# l-band-frontend.net
KiCad netlist of a schematic drawn in EAGLE
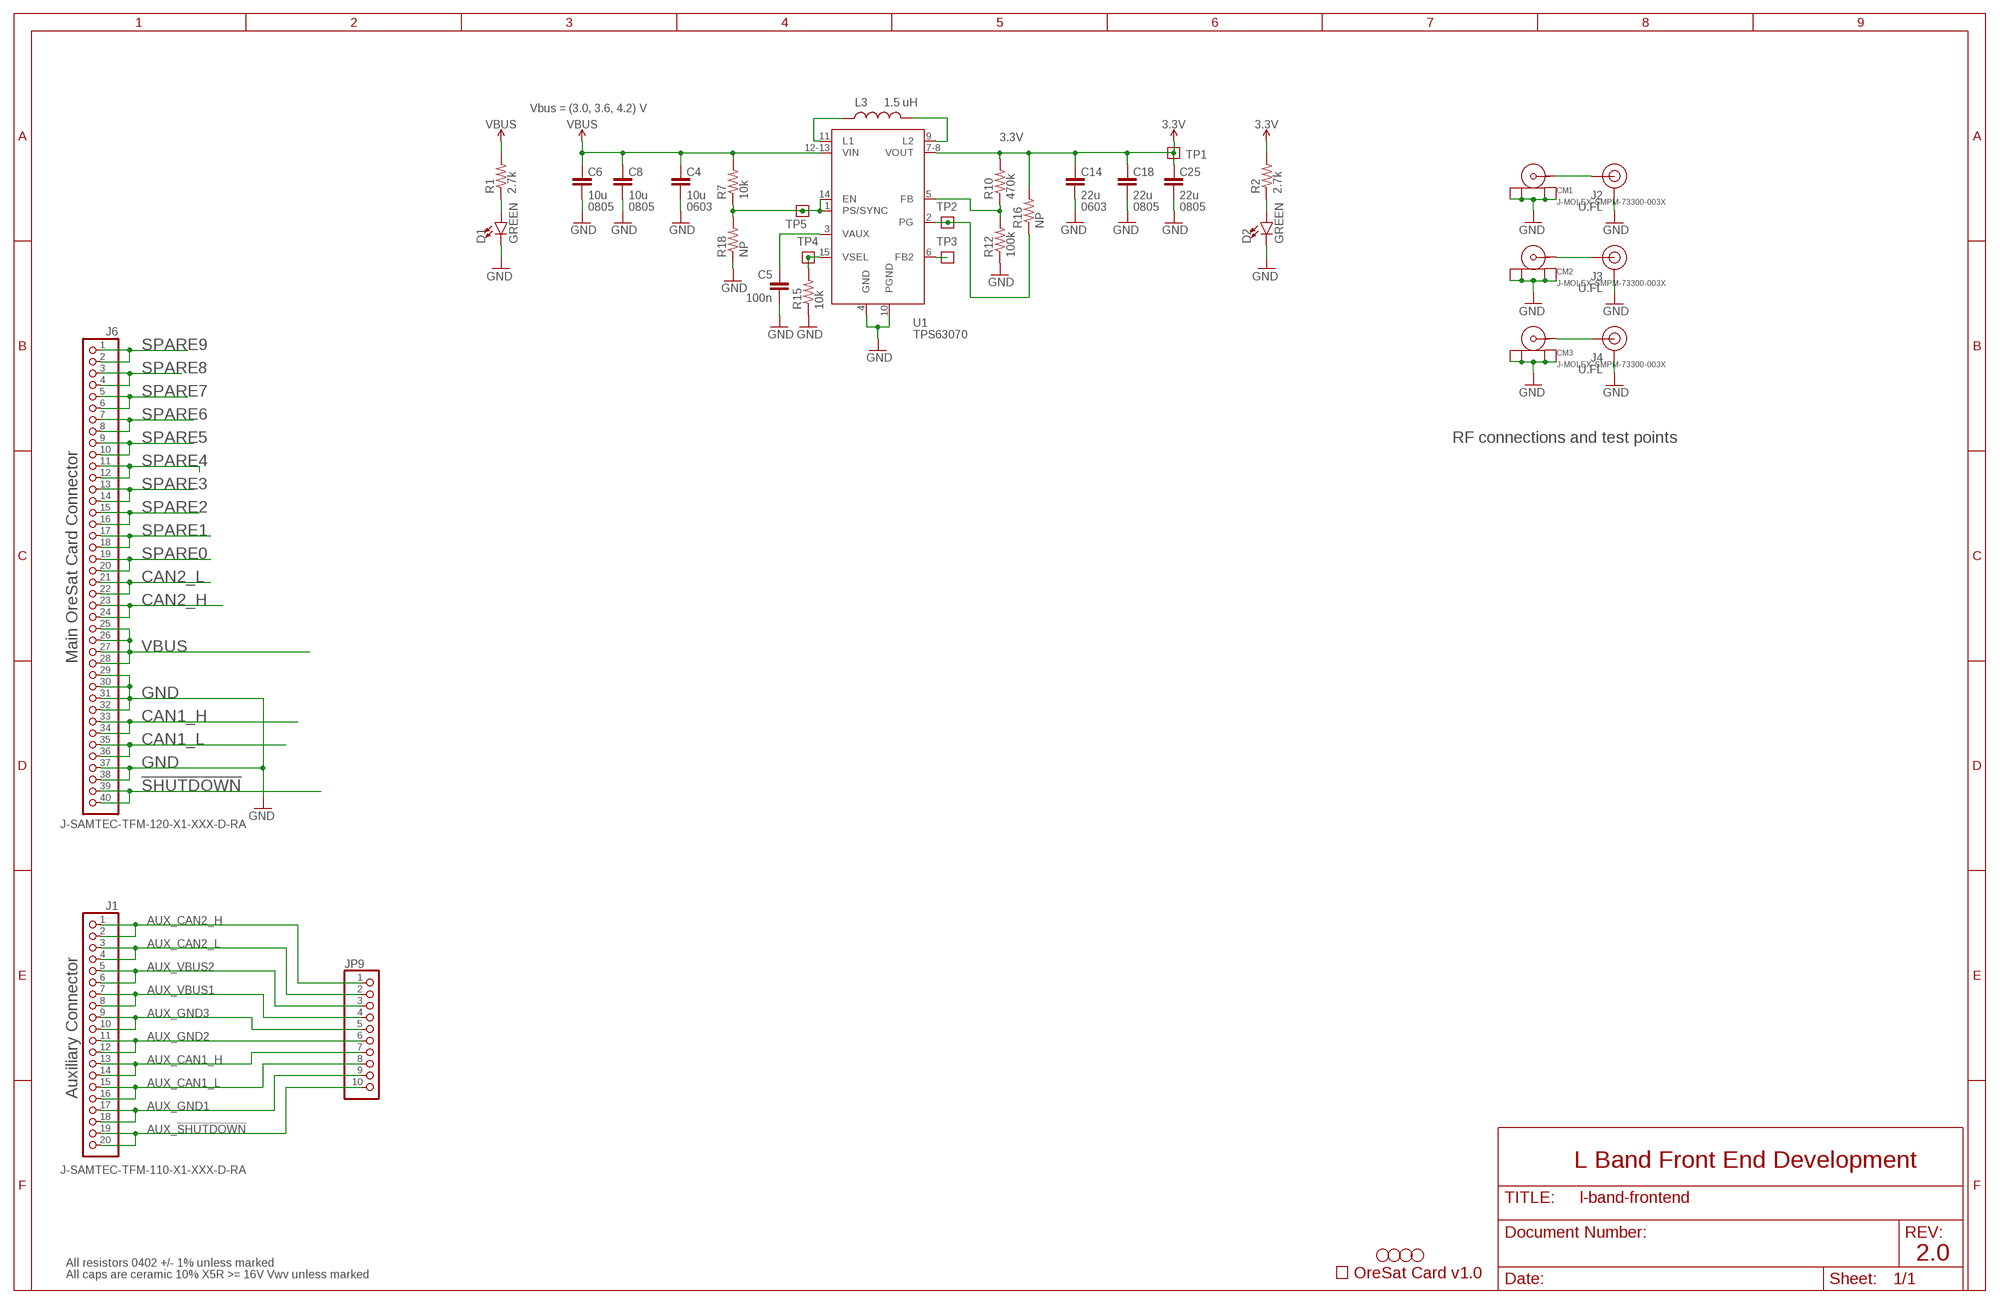
[diagram p0: schematic, sheet 1]

(export (version "E")
  (design (tool "Eeschema 10.0.6"))
  (components
    (comp (ref "C4")
      (value "10u")
      (footprint "eagle-import:.0603-B-NOSILK")
      (fields (field (name "MFR") "Samsung") (field (name "MPN") "CL05B104KO5NNNC"))
      (libsource (lib "eagle-import") (part "C-EU0603-B-NOSILK"))
    )
    (comp (ref "C5")
      (value "100n")
      (footprint "eagle-import:.0402-B-NOSILK")
      (fields (field (name "MFR") "Samsung") (field (name "MPN") "CL05B104KO5NNNC"))
      (libsource (lib "eagle-import") (part "rcl_custom_C-EU0402-B-NOSILK"))
    )
    (comp (ref "C6")
      (value "10u")
      (footprint "eagle-import:.0805-B-NOSILK")
      (libsource (lib "eagle-import") (part "C-EU0805-B-NOSILK"))
    )
    (comp (ref "C8")
      (value "10u")
      (footprint "eagle-import:.0805-B-NOSILK")
      (libsource (lib "eagle-import") (part "C-EU0805-B-NOSILK"))
    )
    (comp (ref "C14")
      (value "22u")
      (footprint "eagle-import:.0603-B-NOSILK")
      (fields (field (name "MFR") "Samsung") (field (name "MPN") "CL05B104KO5NNNC"))
      (libsource (lib "eagle-import") (part "C-EU0603-B-NOSILK"))
    )
    (comp (ref "C18")
      (value "22u")
      (footprint "eagle-import:.0805-B-NOSILK")
      (libsource (lib "eagle-import") (part "C-EU0805-B-NOSILK"))
    )
    (comp (ref "C25")
      (value "22u")
      (footprint "eagle-import:.0805-B-NOSILK")
      (libsource (lib "eagle-import") (part "C-EU0805-B-NOSILK"))
    )
    (comp (ref "CARD")
      (value "ORESAT-CARD-V0.5")
      (footprint "eagle-import:ORESAT-CARD-V1.0")
      (libsource (lib "eagle-import") (part "ORESAT-CARD-V0.5"))
    )
    (comp (ref "CM1")
      (value "J-MOLEX-SMPM-73300-003X")
      (footprint "eagle-import:J-MOLEX-SMPM-073300-003X")
      (libsource (lib "eagle-import") (part "J-MOLEX-SMPM-73300-003X"))
    )
    (comp (ref "CM2")
      (value "J-MOLEX-SMPM-73300-003X")
      (footprint "eagle-import:J-MOLEX-SMPM-073300-003X")
      (libsource (lib "eagle-import") (part "J-MOLEX-SMPM-73300-003X"))
    )
    (comp (ref "CM3")
      (value "J-MOLEX-SMPM-73300-003X")
      (footprint "eagle-import:J-MOLEX-SMPM-073300-003X")
      (libsource (lib "eagle-import") (part "J-MOLEX-SMPM-73300-003X"))
    )
    (comp (ref "D1")
      (value "GREEN")
      (footprint "eagle-import:LED-0603")
      (libsource (lib "eagle-import") (part "LED-GREEN0603"))
    )
    (comp (ref "D2")
      (value "GREEN")
      (footprint "eagle-import:LED-0603")
      (libsource (lib "eagle-import") (part "LED-GREEN0603"))
    )
    (comp (ref "H1")
      (value "STAND-OFFTIGHT")
      (footprint "eagle-import:STAND-OFF-TIGHT")
      (libsource (lib "eagle-import") (part "STAND-OFFTIGHT"))
    )
    (comp (ref "H2")
      (value "STAND-OFFTIGHT")
      (footprint "eagle-import:STAND-OFF-TIGHT")
      (libsource (lib "eagle-import") (part "STAND-OFFTIGHT"))
    )
    (comp (ref "H3")
      (value "STAND-OFFTIGHT")
      (footprint "eagle-import:STAND-OFF-TIGHT")
      (libsource (lib "eagle-import") (part "STAND-OFFTIGHT"))
    )
    (comp (ref "H4")
      (value "STAND-OFFTIGHT")
      (footprint "eagle-import:STAND-OFF-TIGHT")
      (libsource (lib "eagle-import") (part "STAND-OFFTIGHT"))
    )
    (comp (ref "J1")
      (value "J-SAMTEC-TFM-110-X1-XXX-D-RA")
      (footprint "eagle-import:J-SAMTEC-TFM-110-X1-XXX-D-RA")
      (fields (field (name "MFR") "Samtec") (field (name "MPN") "TFM-110-01-L-D-RA "))
      (libsource (lib "eagle-import") (part "J-SAMTEC-TFM-110-X1-XXX-D-RA"))
    )
    (comp (ref "J2")
      (value "U.FL")
      (footprint "eagle-import:U.FL")
      (libsource (lib "eagle-import") (part "U.FL2PIN"))
    )
    (comp (ref "J3")
      (value "U.FL")
      (footprint "eagle-import:U.FL")
      (libsource (lib "eagle-import") (part "U.FL2PIN"))
    )
    (comp (ref "J4")
      (value "U.FL")
      (footprint "eagle-import:U.FL")
      (libsource (lib "eagle-import") (part "U.FL2PIN"))
    )
    (comp (ref "J6")
      (value "J-SAMTEC-TFM-120-X1-XXX-D-RA")
      (footprint "eagle-import:J-SAMTEC-TFM-120-X1-XXX-D-RA")
      (fields (field (name "MFR") "Samtec") (field (name "MPN") "TFM-120-01-L-D-RA"))
      (libsource (lib "eagle-import") (part "J-SAMTEC-TFM-120-X1-XXX-D-RA"))
    )
    (comp (ref "JP9")
      (value "PINHD-1X10")
      (footprint "eagle-import:1X10")
      (libsource (lib "eagle-import") (part "PINHD-1X10"))
    )
    (comp (ref "L3")
      (value "1.5 uH")
      (footprint "eagle-import:L-COILCRAFT-XFL4020")
      (fields (field (name "MFR") "Coilcraft") (field (name "MPN") "XFL4020-152ME"))
      (libsource (lib "eagle-import") (part "L-COILCRAFT-XFL4020"))
    )
    (comp (ref "R1")
      (value "2.7k")
      (footprint "eagle-import:.0402-B-NOSILK")
      (fields (field (name "MFR") "Samsung") (field (name "MPN") "RC1005F6653CS"))
      (libsource (lib "eagle-import") (part "R-US_0402-B-NOSILK"))
    )
    (comp (ref "R2")
      (value "2.7k")
      (footprint "eagle-import:.0402-B-NOSILK")
      (fields (field (name "MFR") "Samsung") (field (name "MPN") "RC1005F6653CS"))
      (libsource (lib "eagle-import") (part "R-US_0402-B-NOSILK"))
    )
    (comp (ref "R7")
      (value "10k")
      (footprint "eagle-import:.0402-B-NOSILK")
      (fields (field (name "MFR") "Samsung") (field (name "MPN") "RC1005F6653CS"))
      (libsource (lib "eagle-import") (part "R-US_0402-B-NOSILK"))
    )
    (comp (ref "R10")
      (value "470k")
      (footprint "eagle-import:.0402-B-NOSILK")
      (fields (field (name "MFR") "Samsung") (field (name "MPN") "RC1005F6653CS"))
      (libsource (lib "eagle-import") (part "R-US_0402-B-NOSILK"))
    )
    (comp (ref "R12")
      (value "100k")
      (footprint "eagle-import:.0402-B-NOSILK")
      (fields (field (name "MFR") "Samsung") (field (name "MPN") "RC1005F6653CS"))
      (libsource (lib "eagle-import") (part "R-US_0402-B-NOSILK"))
    )
    (comp (ref "R15")
      (value "10k")
      (footprint "eagle-import:.0402-B-NOSILK")
      (fields (field (name "MFR") "Samsung") (field (name "MPN") "RC1005F6653CS"))
      (libsource (lib "eagle-import") (part "R-US_0402-B-NOSILK"))
    )
    (comp (ref "R16")
      (value "NP")
      (footprint "eagle-import:.0402-B-NOSILK")
      (fields (field (name "MFR") "Samsung") (field (name "MPN") "RC1005F6653CS"))
      (libsource (lib "eagle-import") (part "R-US_0402-B-NOSILK"))
    )
    (comp (ref "R18")
      (value "NP")
      (footprint "eagle-import:.0402-B-NOSILK")
      (fields (field (name "MFR") "Samsung") (field (name "MPN") "RC1005F6653CS"))
      (libsource (lib "eagle-import") (part "R-US_0402-B-NOSILK"))
    )
    (comp (ref "TP1")
      (value "TEST-POINT")
      (footprint "eagle-import:2MM-TEST-POINT")
      (libsource (lib "eagle-import") (part "TEST-POINT"))
    )
    (comp (ref "TP2")
      (value "TEST-POINT")
      (footprint "eagle-import:2MM-TEST-POINT")
      (libsource (lib "eagle-import") (part "TEST-POINT"))
    )
    (comp (ref "TP3")
      (value "TEST-POINT")
      (footprint "eagle-import:2MM-TEST-POINT")
      (libsource (lib "eagle-import") (part "TEST-POINT"))
    )
    (comp (ref "TP4")
      (value "TEST-POINT")
      (footprint "eagle-import:2MM-TEST-POINT")
      (libsource (lib "eagle-import") (part "TEST-POINT"))
    )
    (comp (ref "TP5")
      (value "TEST-POINT")
      (footprint "eagle-import:2MM-TEST-POINT")
      (libsource (lib "eagle-import") (part "TEST-POINT"))
    )
    (comp (ref "U1")
      (value "TPS63070")
      (footprint "eagle-import:TPS63070X")
      (fields (field (name "MFR") "TI"))
      (libsource (lib "eagle-import") (part "TPS63070X"))
    )
  )
  (nets
    (net (code "1") (name "/AUX_CAN1_H") (class "Default")
      (node (ref "J1") (pin "13") (pinfunction "13_13") (pintype "passive"))
      (node (ref "J1") (pin "14") (pinfunction "14_14") (pintype "passive"))
      (node (ref "JP9") (pin "7") (pinfunction "7_7") (pintype "passive"))
    )
    (net (code "2") (name "/AUX_CAN1_L") (class "Default")
      (node (ref "J1") (pin "15") (pinfunction "15_15") (pintype "passive"))
      (node (ref "J1") (pin "16") (pinfunction "16_16") (pintype "passive"))
      (node (ref "JP9") (pin "8") (pinfunction "8_8") (pintype "passive"))
    )
    (net (code "3") (name "/AUX_CAN2_H") (class "Default")
      (node (ref "J1") (pin "1") (pinfunction "1_1") (pintype "passive"))
      (node (ref "J1") (pin "2") (pinfunction "2_2") (pintype "passive"))
      (node (ref "JP9") (pin "1") (pinfunction "1_1") (pintype "passive"))
    )
    (net (code "4") (name "/AUX_CAN2_L") (class "Default")
      (node (ref "J1") (pin "3") (pinfunction "3_3") (pintype "passive"))
      (node (ref "J1") (pin "4") (pinfunction "4_4") (pintype "passive"))
      (node (ref "JP9") (pin "2") (pinfunction "2_2") (pintype "passive"))
    )
    (net (code "5") (name "/AUX_GND1") (class "Default")
      (node (ref "J1") (pin "17") (pinfunction "17_17") (pintype "passive"))
      (node (ref "J1") (pin "18") (pinfunction "18_18") (pintype "passive"))
      (node (ref "JP9") (pin "9") (pinfunction "9_9") (pintype "passive"))
    )
    (net (code "6") (name "/AUX_GND2") (class "Default")
      (node (ref "J1") (pin "11") (pinfunction "11_11") (pintype "passive"))
      (node (ref "J1") (pin "12") (pinfunction "12_12") (pintype "passive"))
      (node (ref "JP9") (pin "6") (pinfunction "6_6") (pintype "passive"))
    )
    (net (code "7") (name "/AUX_GND3") (class "Default")
      (node (ref "J1") (pin "10") (pinfunction "10_10") (pintype "passive"))
      (node (ref "J1") (pin "9") (pinfunction "9_9") (pintype "passive"))
      (node (ref "JP9") (pin "5") (pinfunction "5_5") (pintype "passive"))
    )
    (net (code "8") (name "/AUX_VBUS1") (class "Default")
      (node (ref "J1") (pin "7") (pinfunction "7_7") (pintype "passive"))
      (node (ref "J1") (pin "8") (pinfunction "8_8") (pintype "passive"))
      (node (ref "JP9") (pin "4") (pinfunction "4_4") (pintype "passive"))
    )
    (net (code "9") (name "/AUX_VBUS2") (class "Default")
      (node (ref "J1") (pin "5") (pinfunction "5_5") (pintype "passive"))
      (node (ref "J1") (pin "6") (pinfunction "6_6") (pintype "passive"))
      (node (ref "JP9") (pin "3") (pinfunction "3_3") (pintype "passive"))
    )
    (net (code "10") (name "/AUX_~{SHUTDOWN}") (class "Default")
      (node (ref "J1") (pin "19") (pinfunction "19_19") (pintype "passive"))
      (node (ref "J1") (pin "20") (pinfunction "20_20") (pintype "passive"))
      (node (ref "JP9") (pin "10") (pinfunction "10_10") (pintype "passive"))
    )
    (net (code "11") (name "/CAN1_H") (class "Default")
      (node (ref "J6") (pin "33") (pinfunction "33_33") (pintype "passive"))
      (node (ref "J6") (pin "34") (pinfunction "34_34") (pintype "passive"))
    )
    (net (code "12") (name "/CAN1_L") (class "Default")
      (node (ref "J6") (pin "35") (pinfunction "35_35") (pintype "passive"))
      (node (ref "J6") (pin "36") (pinfunction "36_36") (pintype "passive"))
    )
    (net (code "13") (name "/CAN2_H") (class "Default")
      (node (ref "J6") (pin "23") (pinfunction "23_23") (pintype "passive"))
      (node (ref "J6") (pin "24") (pinfunction "24_24") (pintype "passive"))
    )
    (net (code "14") (name "/CAN2_L") (class "Default")
      (node (ref "J6") (pin "21") (pinfunction "21_21") (pintype "passive"))
      (node (ref "J6") (pin "22") (pinfunction "22_22") (pintype "passive"))
    )
    (net (code "15") (name "/SPARE0") (class "Default")
      (node (ref "J6") (pin "19") (pinfunction "19_19") (pintype "passive"))
      (node (ref "J6") (pin "20") (pinfunction "20_20") (pintype "passive"))
    )
    (net (code "16") (name "/SPARE1") (class "Default")
      (node (ref "J6") (pin "17") (pinfunction "17_17") (pintype "passive"))
      (node (ref "J6") (pin "18") (pinfunction "18_18") (pintype "passive"))
    )
    (net (code "17") (name "/SPARE2") (class "Default")
      (node (ref "J6") (pin "15") (pinfunction "15_15") (pintype "passive"))
      (node (ref "J6") (pin "16") (pinfunction "16_16") (pintype "passive"))
    )
    (net (code "18") (name "/SPARE3") (class "Default")
      (node (ref "J6") (pin "13") (pinfunction "13_13") (pintype "passive"))
      (node (ref "J6") (pin "14") (pinfunction "14_14") (pintype "passive"))
    )
    (net (code "19") (name "/SPARE4") (class "Default")
      (node (ref "J6") (pin "11") (pinfunction "11_11") (pintype "passive"))
      (node (ref "J6") (pin "12") (pinfunction "12_12") (pintype "passive"))
    )
    (net (code "20") (name "/SPARE5") (class "Default")
      (node (ref "J6") (pin "10") (pinfunction "10_10") (pintype "passive"))
      (node (ref "J6") (pin "9") (pinfunction "9_9") (pintype "passive"))
    )
    (net (code "21") (name "/SPARE6") (class "Default")
      (node (ref "J6") (pin "7") (pinfunction "7_7") (pintype "passive"))
      (node (ref "J6") (pin "8") (pinfunction "8_8") (pintype "passive"))
    )
    (net (code "22") (name "/SPARE7") (class "Default")
      (node (ref "J6") (pin "5") (pinfunction "5_5") (pintype "passive"))
      (node (ref "J6") (pin "6") (pinfunction "6_6") (pintype "passive"))
    )
    (net (code "23") (name "/SPARE8") (class "Default")
      (node (ref "J6") (pin "3") (pinfunction "3_3") (pintype "passive"))
      (node (ref "J6") (pin "4") (pinfunction "4_4") (pintype "passive"))
    )
    (net (code "24") (name "/SPARE9") (class "Default")
      (node (ref "J6") (pin "1") (pinfunction "1_1") (pintype "passive"))
      (node (ref "J6") (pin "2") (pinfunction "2_2") (pintype "passive"))
    )
    (net (code "25") (name "/~{SHUTDOWN}") (class "Default")
      (node (ref "J6") (pin "39") (pinfunction "39_39") (pintype "passive"))
      (node (ref "J6") (pin "40") (pinfunction "40_40") (pintype "passive"))
    )
    (net (code "26") (name "3.3V") (class "Default")
      (node (ref "C14") (pin "1") (pinfunction "1_1") (pintype "passive"))
      (node (ref "C18") (pin "1") (pinfunction "1_1") (pintype "passive"))
      (node (ref "C25") (pin "1") (pinfunction "1_1") (pintype "passive"))
      (node (ref "R10") (pin "2") (pinfunction "2_2") (pintype "passive"))
      (node (ref "R16") (pin "2") (pinfunction "2_2") (pintype "passive"))
      (node (ref "R2") (pin "2") (pinfunction "2_2") (pintype "passive"))
      (node (ref "TP1") (pin "1") (pinfunction "1_1") (pintype "passive"))
      (node (ref "U1") (pin "7-8") (pinfunction "VOUT_7-8") (pintype "power_in"))
    )
    (net (code "27") (name "GND") (class "Default")
      (node (ref "C14") (pin "2") (pinfunction "2_2") (pintype "passive"))
      (node (ref "C18") (pin "2") (pinfunction "2_2") (pintype "passive"))
      (node (ref "C25") (pin "2") (pinfunction "2_2") (pintype "passive"))
      (node (ref "C4") (pin "2") (pinfunction "2_2") (pintype "passive"))
      (node (ref "C5") (pin "2") (pinfunction "2_2") (pintype "passive"))
      (node (ref "C6") (pin "2") (pinfunction "2_2") (pintype "passive"))
      (node (ref "C8") (pin "2") (pinfunction "2_2") (pintype "passive"))
      (node (ref "CM1") (pin "P$1") (pinfunction "SHIELD3_P$1") (pintype "passive"))
      (node (ref "CM1") (pin "P$2") (pinfunction "SHIELD2_P$2") (pintype "passive"))
      (node (ref "CM1") (pin "P$3") (pinfunction "SHIELD1_P$3") (pintype "passive"))
      (node (ref "CM1") (pin "P$4") (pinfunction "SHIELD_P$4") (pintype "passive"))
      (node (ref "CM2") (pin "P$1") (pinfunction "SHIELD3_P$1") (pintype "passive"))
      (node (ref "CM2") (pin "P$2") (pinfunction "SHIELD2_P$2") (pintype "passive"))
      (node (ref "CM2") (pin "P$3") (pinfunction "SHIELD1_P$3") (pintype "passive"))
      (node (ref "CM2") (pin "P$4") (pinfunction "SHIELD_P$4") (pintype "passive"))
      (node (ref "CM3") (pin "P$1") (pinfunction "SHIELD3_P$1") (pintype "passive"))
      (node (ref "CM3") (pin "P$2") (pinfunction "SHIELD2_P$2") (pintype "passive"))
      (node (ref "CM3") (pin "P$3") (pinfunction "SHIELD1_P$3") (pintype "passive"))
      (node (ref "CM3") (pin "P$4") (pinfunction "SHIELD_P$4") (pintype "passive"))
      (node (ref "D1") (pin "C") (pinfunction "C_C") (pintype "passive"))
      (node (ref "D2") (pin "C") (pinfunction "C_C") (pintype "passive"))
      (node (ref "J2") (pin "1") (pinfunction "GND_1") (pintype "bidirectional"))
      (node (ref "J2") (pin "2") (pinfunction "GND_2") (pintype "bidirectional"))
      (node (ref "J3") (pin "1") (pinfunction "GND_1") (pintype "bidirectional"))
      (node (ref "J3") (pin "2") (pinfunction "GND_2") (pintype "bidirectional"))
      (node (ref "J4") (pin "1") (pinfunction "GND_1") (pintype "bidirectional"))
      (node (ref "J4") (pin "2") (pinfunction "GND_2") (pintype "bidirectional"))
      (node (ref "J6") (pin "29") (pinfunction "29_29") (pintype "passive"))
      (node (ref "J6") (pin "30") (pinfunction "30_30") (pintype "passive"))
      (node (ref "J6") (pin "31") (pinfunction "31_31") (pintype "passive"))
      (node (ref "J6") (pin "32") (pinfunction "32_32") (pintype "passive"))
      (node (ref "J6") (pin "37") (pinfunction "37_37") (pintype "passive"))
      (node (ref "J6") (pin "38") (pinfunction "38_38") (pintype "passive"))
      (node (ref "R12") (pin "1") (pinfunction "1_1") (pintype "passive"))
      (node (ref "R15") (pin "1") (pinfunction "1_1") (pintype "passive"))
      (node (ref "R18") (pin "1") (pinfunction "1_1") (pintype "passive"))
      (node (ref "U1") (pin "10") (pinfunction "PGND_10") (pintype "power_in"))
      (node (ref "U1") (pin "4") (pinfunction "GND_4") (pintype "power_in"))
    )
    (net (code "28") (name "Net-(CM1-CENTER)") (class "Default")
      (node (ref "CM1") (pin "RF") (pinfunction "CENTER_RF") (pintype "passive"))
      (node (ref "J2") (pin "FEED") (pinfunction "SIGNAL_FEED") (pintype "bidirectional"))
    )
    (net (code "29") (name "Net-(CM2-CENTER)") (class "Default")
      (node (ref "CM2") (pin "RF") (pinfunction "CENTER_RF") (pintype "passive"))
      (node (ref "J3") (pin "FEED") (pinfunction "SIGNAL_FEED") (pintype "bidirectional"))
    )
    (net (code "30") (name "Net-(CM3-CENTER)") (class "Default")
      (node (ref "CM3") (pin "RF") (pinfunction "CENTER_RF") (pintype "passive"))
      (node (ref "J4") (pin "FEED") (pinfunction "SIGNAL_FEED") (pintype "bidirectional"))
    )
    (net (code "31") (name "Net-(D1-PadA)") (class "Default")
      (node (ref "D1") (pin "A") (pinfunction "A_A") (pintype "passive"))
      (node (ref "R1") (pin "1") (pinfunction "1_1") (pintype "passive"))
    )
    (net (code "32") (name "Net-(D2-PadA)") (class "Default")
      (node (ref "D2") (pin "A") (pinfunction "A_A") (pintype "passive"))
      (node (ref "R2") (pin "1") (pinfunction "1_1") (pintype "passive"))
    )
    (net (code "33") (name "Net-(U1-EN)") (class "Default")
      (node (ref "R18") (pin "2") (pinfunction "2_2") (pintype "passive"))
      (node (ref "R7") (pin "1") (pinfunction "1_1") (pintype "passive"))
      (node (ref "TP5") (pin "1") (pinfunction "1_1") (pintype "passive"))
      (node (ref "U1") (pin "1") (pinfunction "PS/SYNC_1") (pintype "input"))
      (node (ref "U1") (pin "14") (pinfunction "EN_14") (pintype "input"))
    )
    (net (code "34") (name "Net-(U1-FB)") (class "Default")
      (node (ref "R10") (pin "1") (pinfunction "1_1") (pintype "passive"))
      (node (ref "R12") (pin "2") (pinfunction "2_2") (pintype "passive"))
      (node (ref "U1") (pin "5") (pinfunction "FB_5") (pintype "passive"))
    )
    (net (code "35") (name "Net-(U1-FB2)") (class "Default")
      (node (ref "TP3") (pin "1") (pinfunction "1_1") (pintype "passive"))
      (node (ref "U1") (pin "6") (pinfunction "FB2_6") (pintype "passive"))
    )
    (net (code "36") (name "Net-(U1-L1)") (class "Default")
      (node (ref "L3") (pin "1") (pinfunction "1_1") (pintype "passive"))
      (node (ref "U1") (pin "11") (pinfunction "L1_11") (pintype "passive"))
    )
    (net (code "37") (name "Net-(U1-L2)") (class "Default")
      (node (ref "L3") (pin "2") (pinfunction "2_2") (pintype "passive"))
      (node (ref "U1") (pin "9") (pinfunction "L2_9") (pintype "passive"))
    )
    (net (code "38") (name "Net-(U1-PG)") (class "Default")
      (node (ref "R16") (pin "1") (pinfunction "1_1") (pintype "passive"))
      (node (ref "TP2") (pin "1") (pinfunction "1_1") (pintype "passive"))
      (node (ref "U1") (pin "2") (pinfunction "PG_2") (pintype "open_collector"))
    )
    (net (code "39") (name "Net-(U1-VAUX)") (class "Default")
      (node (ref "C5") (pin "1") (pinfunction "1_1") (pintype "passive"))
      (node (ref "U1") (pin "3") (pinfunction "VAUX_3") (pintype "output"))
    )
    (net (code "40") (name "Net-(U1-VSEL)") (class "Default")
      (node (ref "R15") (pin "2") (pinfunction "2_2") (pintype "passive"))
      (node (ref "TP4") (pin "1") (pinfunction "1_1") (pintype "passive"))
      (node (ref "U1") (pin "15") (pinfunction "VSEL_15") (pintype "input"))
    )
    (net (code "41") (name "VBUS") (class "Default")
      (node (ref "C4") (pin "1") (pinfunction "1_1") (pintype "passive"))
      (node (ref "C6") (pin "1") (pinfunction "1_1") (pintype "passive"))
      (node (ref "C8") (pin "1") (pinfunction "1_1") (pintype "passive"))
      (node (ref "J6") (pin "25") (pinfunction "25_25") (pintype "passive"))
      (node (ref "J6") (pin "26") (pinfunction "26_26") (pintype "passive"))
      (node (ref "J6") (pin "27") (pinfunction "27_27") (pintype "passive"))
      (node (ref "J6") (pin "28") (pinfunction "28_28") (pintype "passive"))
      (node (ref "R1") (pin "2") (pinfunction "2_2") (pintype "passive"))
      (node (ref "R7") (pin "2") (pinfunction "2_2") (pintype "passive"))
      (node (ref "U1") (pin "12-13") (pinfunction "VIN_12-13") (pintype "power_in"))
    )
  )
)
